# MCP1700T-3302.net
KiCad netlist of a schematic drawn in Altium Designer
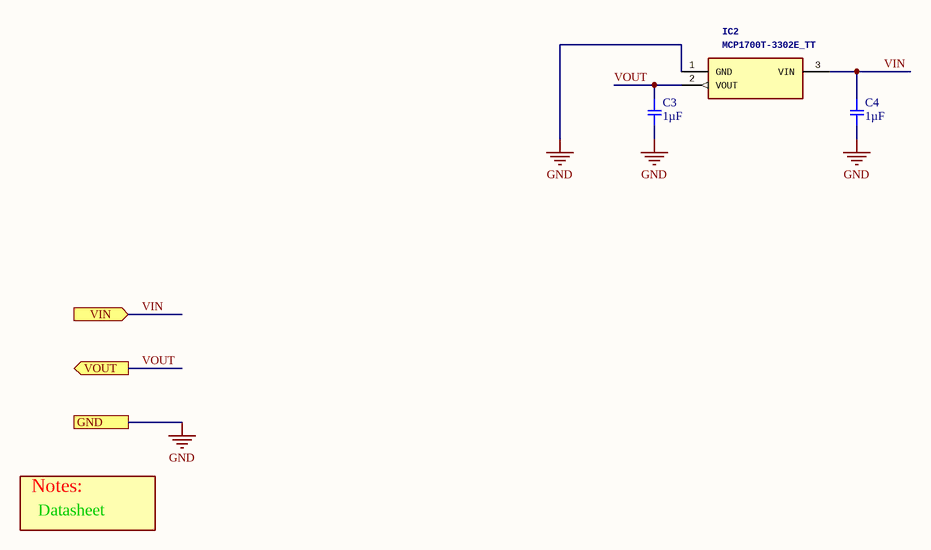
[diagram p0: MCP1700T-3302.SchDoc]

(export (version "E")
  (design (tool "Eeschema 10.0.6"))
  (components
    (comp (ref "C3")
      (value "1µF")
      (footprint "SMD-0402C")
      (description "CAP CER 1UF 10V X7S 0402")
      (fields
        (field (name "DIGI-KEY PART NUMBER") "490-13409-1-ND")
        (field (name "PART NUMBER") "GCM155C71A105KE38D")
      )
      (libsource (lib "capacitor_murata_0402") (part "GCM155C71A105KE38D"))
    )
    (comp (ref "C4")
      (value "1µF")
      (footprint "SMD-0402C")
      (description "CAP CER 1UF 10V X7S 0402")
      (fields
        (field (name "DIGI-KEY PART NUMBER") "490-13409-1-ND")
        (field (name "PART NUMBER") "GCM155C71A105KE38D")
      )
      (libsource (lib "capacitor_murata_0402") (part "GCM155C71A105KE38D"))
    )
    (comp (ref "IC2")
      (value "MCP1700T-3302E_TT")
      (footprint "SOT23")
      (description "LDO Voltage Regulator 250mA 3.3V")
      (fields
        (field (name "MANUFACTURER_PART_NUMBER") "MCP1700T-3302E/TT")
        (field (name "MOUSER_PART_NUMBER") "579-MCP1700T3302E/TT")
      )
      (libsource (lib "HW-General-Lib") (part "MCP1700T-3302"))
    )
  )
  (nets
    (net (code "1") (name "/VIN") (class "Default")
      (node (ref "C4") (pin "1") (pinfunction "1_1") (pintype "passive"))
      (node (ref "IC2") (pin "3") (pinfunction "VIN_3") (pintype "passive"))
    )
    (net (code "2") (name "/VOUT") (class "Default")
      (node (ref "C3") (pin "1") (pinfunction "1_1") (pintype "passive"))
      (node (ref "IC2") (pin "2") (pinfunction "VOUT_2") (pintype "output"))
    )
    (net (code "3") (name "GND") (class "Default")
      (node (ref "C3") (pin "2") (pinfunction "2_2") (pintype "passive"))
      (node (ref "C4") (pin "2") (pinfunction "2_2") (pintype "passive"))
      (node (ref "IC2") (pin "1") (pinfunction "GND_1") (pintype "power_in"))
    )
  )
)
